# Simple-Transmitter-BC547.net
KiCad netlist of a schematic drawn in EAGLE
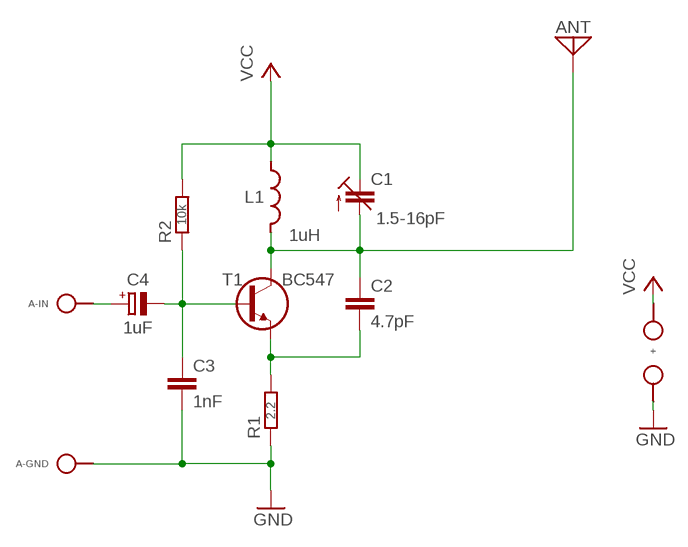
[diagram p0: schematic, sheet 1]

(export (version "E")
  (design (tool "Eeschema 10.0.6"))
  (components
    (comp (ref "+")
      (value "SPAD")
      (footprint "eagle-import:SPAD")
      (libsource (lib "eagle-import") (part "SPAD"))
    )
    (comp (ref "A-GND")
      (value "SPAD")
      (footprint "eagle-import:SPAD")
      (libsource (lib "eagle-import") (part "SPAD"))
    )
    (comp (ref "A-IN")
      (value "SPAD")
      (footprint "eagle-import:SPAD")
      (libsource (lib "eagle-import") (part "SPAD"))
    )
    (comp (ref "ANT")
      (value "ANT")
      (footprint "eagle-import:SPAD")
      (libsource (lib "eagle-import") (part "ANT"))
    )
    (comp (ref "C1")
      (value "1.5-16pF")
      (footprint "eagle-import:TRIM808-45")
      (libsource (lib "eagle-import") (part "C-TR-PH20127-45-2P23"))
    )
    (comp (ref "C2")
      (value "4.7pF")
      (footprint "eagle-import:C050-020X036-M")
      (libsource (lib "eagle-import") (part "C050-020X036-M"))
    )
    (comp (ref "C3")
      (value "1nF")
      (footprint "eagle-import:C050-020X036")
      (libsource (lib "eagle-import") (part "C050-020X036"))
    )
    (comp (ref "C4")
      (value "1uF")
      (footprint "eagle-import:E2,5-3")
      (libsource (lib "eagle-import") (part "CPOLE2,5-3"))
    )
    (comp (ref "L1")
      (value "1uH")
      (footprint "eagle-import:L-04_7")
      (libsource (lib "eagle-import") (part "L-SHORT04/7"))
    )
    (comp (ref "R1")
      (value "2.2")
      (footprint "eagle-import:0202V")
      (libsource (lib "eagle-import") (part "R0202V"))
    )
    (comp (ref "R2")
      (value "10k")
      (footprint "eagle-import:0202_5-V")
      (libsource (lib "eagle-import") (part "R0202/5-V"))
    )
    (comp (ref "T1")
      (value "BC547")
      (footprint "eagle-import:TO92-CBE")
      (libsource (lib "eagle-import") (part "BC547CBE"))
    )
    (comp (ref "̶̶")
      (value "SPAD")
      (footprint "eagle-import:SPAD")
      (libsource (lib "eagle-import") (part "SPAD"))
    )
  )
  (nets
    (net (code "1") (name "GND") (class "Default")
      (node (ref "A-GND") (pin "1") (pinfunction "P$1_1") (pintype "bidirectional"))
      (node (ref "C3") (pin "2") (pinfunction "2_2") (pintype "passive"))
      (node (ref "R1") (pin "1") (pinfunction "1_1") (pintype "passive"))
      (node (ref "̶̶") (pin "1") (pinfunction "P$1_1") (pintype "bidirectional"))
    )
    (net (code "2") (name "Net-(A-IN-P$1)") (class "Default")
      (node (ref "A-IN") (pin "1") (pinfunction "P$1_1") (pintype "bidirectional"))
      (node (ref "C4") (pin "+") (pinfunction "+_+") (pintype "passive"))
    )
    (net (code "3") (name "Net-(C1-E)") (class "Default")
      (node (ref "ANT") (pin "1") (pinfunction "1_1") (pintype "output"))
      (node (ref "C1") (pin "2") (pinfunction "E_2") (pintype "passive"))
      (node (ref "C2") (pin "1") (pinfunction "1_1") (pintype "passive"))
      (node (ref "L1") (pin "2") (pinfunction "2_2") (pintype "passive"))
      (node (ref "T1") (pin "C") (pinfunction "C_C") (pintype "passive"))
    )
    (net (code "4") (name "Net-(C2-Pad2)") (class "Default")
      (node (ref "C2") (pin "2") (pinfunction "2_2") (pintype "passive"))
      (node (ref "R1") (pin "2") (pinfunction "2_2") (pintype "passive"))
      (node (ref "T1") (pin "E") (pinfunction "E_E") (pintype "passive"))
    )
    (net (code "5") (name "Net-(C3-Pad1)") (class "Default")
      (node (ref "C3") (pin "1") (pinfunction "1_1") (pintype "passive"))
      (node (ref "C4") (pin "-") (pinfunction "-_-") (pintype "passive"))
      (node (ref "R2") (pin "1") (pinfunction "1_1") (pintype "passive"))
      (node (ref "T1") (pin "B") (pinfunction "B_B") (pintype "passive"))
    )
    (net (code "6") (name "VCC") (class "Default")
      (node (ref "+") (pin "1") (pinfunction "P$1_1") (pintype "bidirectional"))
      (node (ref "C1") (pin "3") (pinfunction "A_3") (pintype "passive"))
      (node (ref "L1") (pin "1") (pinfunction "1_1") (pintype "passive"))
      (node (ref "R2") (pin "2") (pinfunction "2_2") (pintype "passive"))
    )
  )
)
